# pa.net
KiCad netlist of a schematic drawn in Altium Designer
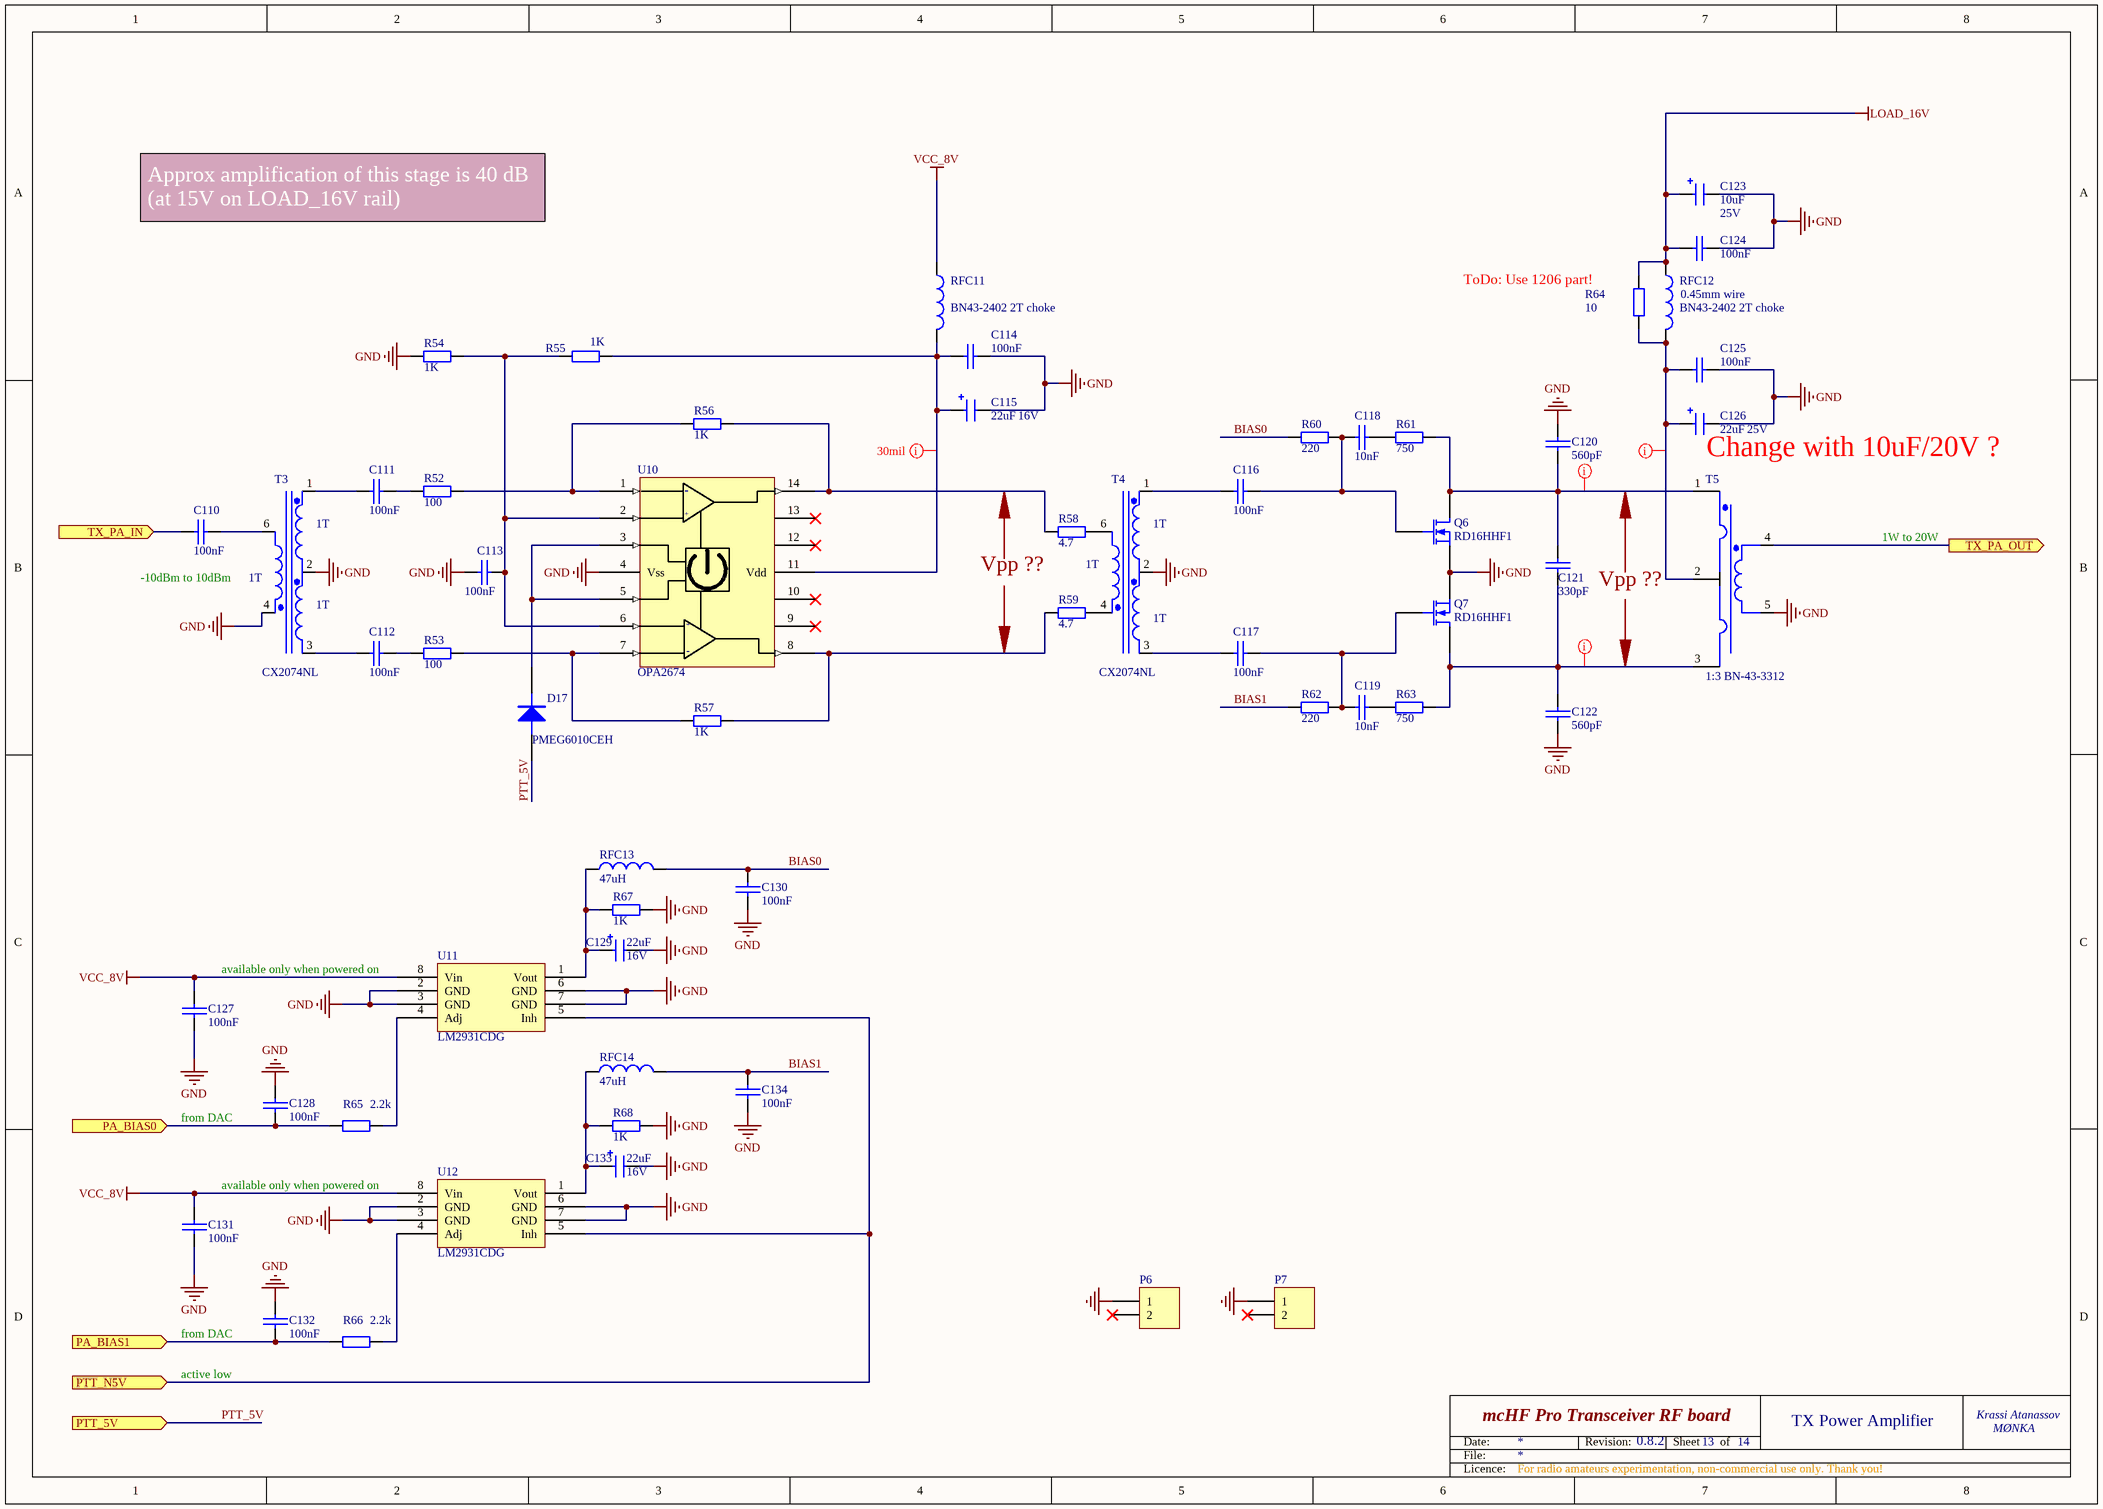
[diagram p0: pa.SchDoc]

(export (version "E")
  (design (tool "Eeschema 10.0.6"))
  (components
    (comp (ref "C110")
      (value "100nF")
      (footprint "0805")
      (description "Capacitor")
      (libsource (lib "mcHF_rf") (part "CAP"))
    )
    (comp (ref "C111")
      (value "100nF")
      (footprint "0805")
      (description "Capacitor")
      (fields (field (name "VOLTAGE") "100V"))
      (libsource (lib "mcHF_rf") (part "CAP"))
    )
    (comp (ref "C112")
      (value "100nF")
      (footprint "0805")
      (description "Capacitor")
      (fields (field (name "VOLTAGE") "100V"))
      (libsource (lib "mcHF_rf") (part "CAP"))
    )
    (comp (ref "C113")
      (value "100nF")
      (footprint "0805")
      (description "Capacitor")
      (fields (field (name "VOLTAGE") "100V"))
      (libsource (lib "mcHF_rf") (part "CAP"))
    )
    (comp (ref "C114")
      (value "100nF")
      (footprint "0805")
      (description "Capacitor")
      (fields (field (name "VOLTAGE") "100V"))
      (libsource (lib "mcHF_rf") (part "CAP"))
    )
    (comp (ref "C115")
      (value "22uF")
      (footprint "1206_Elec_Cap")
      (description "Electrolitic capacitor")
      (fields (field (name "VOLTAGE") "16V"))
      (libsource (lib "mcHF_rf") (part "CAP-POL"))
    )
    (comp (ref "C116")
      (value "100nF")
      (footprint "0805")
      (description "Capacitor")
      (fields (field (name "VOLTAGE") "100V"))
      (libsource (lib "mcHF_rf") (part "CAP"))
    )
    (comp (ref "C117")
      (value "100nF")
      (footprint "0805")
      (description "Capacitor")
      (fields (field (name "VOLTAGE") "100V"))
      (libsource (lib "mcHF_rf") (part "CAP"))
    )
    (comp (ref "C118")
      (value "10nF")
      (footprint "0805")
      (description "Capacitor")
      (fields (field (name "VOLTAGE") "100V"))
      (libsource (lib "mcHF_rf") (part "CAP"))
    )
    (comp (ref "C119")
      (value "10nF")
      (footprint "0805")
      (description "Capacitor")
      (fields (field (name "VOLTAGE") "100V"))
      (libsource (lib "mcHF_rf") (part "CAP"))
    )
    (comp (ref "C120")
      (value "560pF")
      (footprint "0805")
      (description "Capacitor")
      (fields (field (name "VOLTAGE") "100V"))
      (libsource (lib "mcHF_rf") (part "CAP"))
    )
    (comp (ref "C121")
      (value "330pF")
      (footprint "0805")
      (description "Capacitor")
      (fields (field (name "VOLTAGE") "100V"))
      (libsource (lib "mcHF_rf") (part "CAP"))
    )
    (comp (ref "C122")
      (value "560pF")
      (footprint "0805")
      (description "Capacitor")
      (fields (field (name "VOLTAGE") "100V"))
      (libsource (lib "mcHF_rf") (part "CAP"))
    )
    (comp (ref "C123")
      (value "10uF")
      (footprint "1206_Elec_Cap")
      (description "Electrolitic capacitor")
      (fields (field (name "VOLTAGE") "25V"))
      (libsource (lib "mcHF_rf") (part "CAP-POL"))
    )
    (comp (ref "C124")
      (value "100nF")
      (footprint "0805")
      (description "Capacitor")
      (fields (field (name "VOLTAGE") "100V"))
      (libsource (lib "mcHF_rf") (part "CAP"))
    )
    (comp (ref "C125")
      (value "100nF")
      (footprint "0805")
      (description "Capacitor")
      (fields (field (name "VOLTAGE") "100V"))
      (libsource (lib "mcHF_rf") (part "CAP"))
    )
    (comp (ref "C126")
      (value "22uF")
      (footprint "1206_Elec_Cap")
      (description "Electrolitic capacitor")
      (fields (field (name "VOLTAGE") "25V"))
      (libsource (lib "mcHF_rf") (part "CAP-POL"))
    )
    (comp (ref "C127")
      (value "100nF")
      (footprint "0805")
      (description "Capacitor")
      (fields (field (name "VOLTAGE") "100V"))
      (libsource (lib "mcHF_rf") (part "CAP"))
    )
    (comp (ref "C128")
      (value "100nF")
      (footprint "0805")
      (description "Capacitor")
      (libsource (lib "mcHF_rf") (part "CAP"))
    )
    (comp (ref "C129")
      (value "22uF")
      (footprint "1206_Elec_Cap")
      (description "Electrolitic capacitor")
      (fields (field (name "VOLTAGE") "16V"))
      (libsource (lib "mcHF_rf") (part "CAP-POL"))
    )
    (comp (ref "C130")
      (value "100nF")
      (footprint "0805")
      (description "Capacitor")
      (fields (field (name "VOLTAGE") "100V"))
      (libsource (lib "mcHF_rf") (part "CAP"))
    )
    (comp (ref "C131")
      (value "100nF")
      (footprint "0805")
      (description "Capacitor")
      (fields (field (name "VOLTAGE") "100V"))
      (libsource (lib "mcHF_rf") (part "CAP"))
    )
    (comp (ref "C132")
      (value "100nF")
      (footprint "0805")
      (description "Capacitor")
      (libsource (lib "mcHF_rf") (part "CAP"))
    )
    (comp (ref "C133")
      (value "22uF")
      (footprint "1206_Elec_Cap")
      (description "Electrolitic capacitor")
      (fields (field (name "VOLTAGE") "16V"))
      (libsource (lib "mcHF_rf") (part "CAP-POL"))
    )
    (comp (ref "C134")
      (value "100nF")
      (footprint "0805")
      (description "Capacitor")
      (fields (field (name "VOLTAGE") "100V"))
      (libsource (lib "mcHF_rf") (part "CAP"))
    )
    (comp (ref "D17")
      (value "PMEG6010CEH")
      (footprint "SOD87")
      (description "DIODE, SCHOTTKY, 1A, 60V, SOD-123F")
      (libsource (lib "mcHF_rf") (part "PMEG6010CEH"))
    )
    (comp (ref "P6")
      (value "Header 2")
      (footprint "SIP2")
      (description "Header, 2-Pin")
      (libsource (lib "__ui") (part "Header 2"))
    )
    (comp (ref "P7")
      (value "Header 2")
      (footprint "SIP2")
      (description "Header, 2-Pin")
      (libsource (lib "__ui") (part "Header 2"))
    )
    (comp (ref "Q6")
      (value "RD16HHF1")
      (footprint "TO-220RF_flat")
      (description "Silicon RF Power MOS FET")
      (libsource (lib "M_RF") (part "RD16HHF1"))
    )
    (comp (ref "Q7")
      (value "RD16HHF1")
      (footprint "TO-220RF_flat")
      (description "Silicon RF Power MOS FET")
      (libsource (lib "M_RF") (part "RD16HHF1"))
    )
    (comp (ref "R52")
      (value "100")
      (footprint "0805")
      (description "Resistor")
      (libsource (lib "mcHF_rf") (part "RES"))
    )
    (comp (ref "R53")
      (value "100")
      (footprint "0805")
      (description "Resistor")
      (libsource (lib "mcHF_rf") (part "RES"))
    )
    (comp (ref "R54")
      (value "1K")
      (footprint "0805")
      (description "Resistor")
      (libsource (lib "") (part "RES_1"))
    )
    (comp (ref "R55")
      (value "1K")
      (footprint "0805")
      (description "Resistor")
      (libsource (lib "mcHF_rf") (part "RES"))
    )
    (comp (ref "R56")
      (value "1K")
      (footprint "0805")
      (description "Resistor")
      (libsource (lib "mcHF_rf") (part "RES"))
    )
    (comp (ref "R57")
      (value "1K")
      (footprint "0805")
      (description "Resistor")
      (libsource (lib "mcHF_rf") (part "RES"))
    )
    (comp (ref "R58")
      (value "4.7")
      (footprint "0805")
      (description "Resistor")
      (libsource (lib "mcHF_rf") (part "RES"))
    )
    (comp (ref "R59")
      (value "4.7")
      (footprint "0805")
      (description "Resistor")
      (libsource (lib "mcHF_rf") (part "RES"))
    )
    (comp (ref "R60")
      (value "220")
      (footprint "0805")
      (description "Resistor")
      (libsource (lib "mcHF_rf") (part "RES"))
    )
    (comp (ref "R61")
      (value "750")
      (footprint "0805")
      (description "Resistor")
      (libsource (lib "mcHF_rf") (part "RES"))
    )
    (comp (ref "R62")
      (value "220")
      (footprint "0805")
      (description "Resistor")
      (libsource (lib "mcHF_rf") (part "RES"))
    )
    (comp (ref "R63")
      (value "750")
      (footprint "0805")
      (description "Resistor")
      (libsource (lib "mcHF_rf") (part "RES"))
    )
    (comp (ref "R64")
      (value "10")
      (footprint "0805")
      (description "Resistor")
      (libsource (lib "") (part "RES_2"))
    )
    (comp (ref "R65")
      (value "2.2k")
      (footprint "0805")
      (description "Resistor")
      (libsource (lib "") (part "RES_1"))
    )
    (comp (ref "R66")
      (value "2.2k")
      (footprint "0805")
      (description "Resistor")
      (libsource (lib "") (part "RES_1"))
    )
    (comp (ref "R67")
      (value "1K")
      (footprint "0805")
      (description "Resistor")
      (libsource (lib "mcHF_rf") (part "RES"))
    )
    (comp (ref "R68")
      (value "1K")
      (footprint "0805")
      (description "Resistor")
      (libsource (lib "mcHF_rf") (part "RES"))
    )
    (comp (ref "RFC11")
      (value "BN43-2402 2T choke")
      (footprint "F_Bead")
      (description "BN43-2402 1t choke")
      (libsource (lib "mcHF_rf") (part "FER_BEAD"))
    )
    (comp (ref "RFC12")
      (value "BN43-2402 2T choke")
      (footprint "F_Bead")
      (description "BN43-2402 1t choke")
      (libsource (lib "mcHF_rf") (part "FER_BEAD"))
    )
    (comp (ref "RFC13")
      (value "47uH")
      (footprint "0805")
      (description "INDUCTOR, SIGNAL LINE, 4.7UH, 1005")
      (libsource (lib "mcHF_rf") (part "TDK-NLV25T"))
    )
    (comp (ref "RFC14")
      (value "47uH")
      (footprint "0805")
      (description "INDUCTOR, SIGNAL LINE, 4.7UH, 1005")
      (libsource (lib "mcHF_rf") (part "TDK-NLV25T"))
    )
    (comp (ref "T3")
      (value "CX2074NL")
      (footprint "SOP5_NEW1")
      (description "Transformer 4:1")
      (libsource (lib "mcHF_rf") (part "CX2074NL"))
    )
    (comp (ref "T4")
      (value "CX2074NL")
      (footprint "SOP5_NEW1")
      (description "Transformer 4:1")
      (libsource (lib "mcHF_rf") (part "CX2074NL"))
    )
    (comp (ref "T5")
      (value "1:3 BN-43-3312")
      (footprint "PA_OUT_TRM")
      (description "1:3 BN-43-3312 transformer")
      (libsource (lib "__rf") (part "PA_OUT_TR"))
    )
    (comp (ref "U10")
      (value "OPA2674")
      (footprint "SO-14-PRO")
      (description "Dual Wideband, High Output Current\r\nOperational Amplifier with Current Limit")
      (libsource (lib "__rf") (part "OPA2674"))
    )
    (comp (ref "U11")
      (value "LM2931CDG")
      (footprint "SO-8-PRO")
      (description "100 mA, Adjustable Output,  LDO Voltage Regulator with  60 V Load Dump Protection")
      (libsource (lib "mcHF_rf") (part "LM2931CDG"))
    )
    (comp (ref "U12")
      (value "LM2931CDG")
      (footprint "SO-8-PRO")
      (description "100 mA, Adjustable Output,  LDO Voltage Regulator with  60 V Load Dump Protection")
      (libsource (lib "mcHF_rf") (part "LM2931CDG"))
    )
  )
  (nets
    (net (code "1") (name "/BIAS0") (class "Default")
      (node (ref "C130") (pin "2") (pinfunction "2_2") (pintype "passive"))
      (node (ref "R60") (pin "2") (pinfunction "2_2") (pintype "passive"))
      (node (ref "RFC13") (pin "2") (pinfunction "2_2") (pintype "passive"))
    )
    (net (code "2") (name "/BIAS1") (class "Default")
      (node (ref "C134") (pin "2") (pinfunction "2_2") (pintype "passive"))
      (node (ref "R62") (pin "2") (pinfunction "2_2") (pintype "passive"))
      (node (ref "RFC14") (pin "2") (pinfunction "2_2") (pintype "passive"))
    )
    (net (code "3") (name "/PA_BIAS0") (class "Default")
      (node (ref "C128") (pin "1") (pinfunction "1_1") (pintype "passive"))
      (node (ref "R65") (pin "1") (pinfunction "1_1") (pintype "passive"))
    )
    (net (code "4") (name "/PA_BIAS1") (class "Default")
      (node (ref "C132") (pin "2") (pinfunction "2_2") (pintype "passive"))
      (node (ref "R66") (pin "1") (pinfunction "1_1") (pintype "passive"))
    )
    (net (code "5") (name "/PTT_5V") (class "Default")
      (node (ref "D17") (pin "1") (pinfunction "A_1") (pintype "passive"))
    )
    (net (code "6") (name "/PTT_N5V") (class "Default")
      (node (ref "U11") (pin "5") (pinfunction "Inh_5") (pintype "passive"))
      (node (ref "U12") (pin "5") (pinfunction "Inh_5") (pintype "passive"))
    )
    (net (code "7") (name "/TX_PA_IN") (class "Default")
      (node (ref "C110") (pin "2") (pinfunction "2_2") (pintype "passive"))
    )
    (net (code "8") (name "/TX_PA_OUT") (class "Default")
      (node (ref "T5") (pin "4") (pinfunction "Sec+_4") (pintype "passive"))
    )
    (net (code "9") (name "GND") (class "Default")
      (node (ref "C113") (pin "1") (pinfunction "1_1") (pintype "passive"))
      (node (ref "C114") (pin "1") (pinfunction "1_1") (pintype "passive"))
      (node (ref "C115") (pin "2") (pinfunction "2_2") (pintype "passive"))
      (node (ref "C120") (pin "1") (pinfunction "1_1") (pintype "passive"))
      (node (ref "C122") (pin "2") (pinfunction "2_2") (pintype "passive"))
      (node (ref "C123") (pin "2") (pinfunction "2_2") (pintype "passive"))
      (node (ref "C124") (pin "1") (pinfunction "1_1") (pintype "passive"))
      (node (ref "C125") (pin "1") (pinfunction "1_1") (pintype "passive"))
      (node (ref "C126") (pin "2") (pinfunction "2_2") (pintype "passive"))
      (node (ref "C127") (pin "2") (pinfunction "2_2") (pintype "passive"))
      (node (ref "C128") (pin "2") (pinfunction "2_2") (pintype "passive"))
      (node (ref "C129") (pin "2") (pinfunction "2_2") (pintype "passive"))
      (node (ref "C130") (pin "1") (pinfunction "1_1") (pintype "passive"))
      (node (ref "C131") (pin "2") (pinfunction "2_2") (pintype "passive"))
      (node (ref "C132") (pin "1") (pinfunction "1_1") (pintype "passive"))
      (node (ref "C133") (pin "2") (pinfunction "2_2") (pintype "passive"))
      (node (ref "C134") (pin "1") (pinfunction "1_1") (pintype "passive"))
      (node (ref "P6") (pin "1") (pinfunction "1_1") (pintype "passive"))
      (node (ref "P7") (pin "1") (pinfunction "1_1") (pintype "passive"))
      (node (ref "Q6") (pin "2") (pinfunction "S_2") (pintype "passive"))
      (node (ref "Q7") (pin "2") (pinfunction "S_2") (pintype "passive"))
      (node (ref "R54") (pin "1") (pinfunction "1_1") (pintype "passive"))
      (node (ref "R67") (pin "1") (pinfunction "1_1") (pintype "passive"))
      (node (ref "R68") (pin "1") (pinfunction "1_1") (pintype "passive"))
      (node (ref "T3") (pin "2") (pinfunction "SecCmn_2") (pintype "passive"))
      (node (ref "T3") (pin "4") (pinfunction "Pri-_4") (pintype "passive"))
      (node (ref "T4") (pin "2") (pinfunction "SecCmn_2") (pintype "passive"))
      (node (ref "T5") (pin "5") (pinfunction "Sec-_5") (pintype "passive"))
      (node (ref "U10") (pin "4") (pinfunction "Vss_4") (pintype "power_in"))
      (node (ref "U11") (pin "2") (pinfunction "GND_2") (pintype "passive"))
      (node (ref "U11") (pin "3") (pinfunction "GND_3") (pintype "passive"))
      (node (ref "U11") (pin "6") (pinfunction "GND_6") (pintype "passive"))
      (node (ref "U11") (pin "7") (pinfunction "GND_7") (pintype "passive"))
      (node (ref "U12") (pin "2") (pinfunction "GND_2") (pintype "passive"))
      (node (ref "U12") (pin "3") (pinfunction "GND_3") (pintype "passive"))
      (node (ref "U12") (pin "6") (pinfunction "GND_6") (pintype "passive"))
      (node (ref "U12") (pin "7") (pinfunction "GND_7") (pintype "passive"))
    )
    (net (code "10") (name "LOAD_16V") (class "Default")
      (node (ref "C123") (pin "1") (pinfunction "1_1") (pintype "passive"))
      (node (ref "C124") (pin "2") (pinfunction "2_2") (pintype "passive"))
      (node (ref "R64") (pin "2") (pinfunction "2_2") (pintype "passive"))
      (node (ref "RFC12") (pin "1") (pinfunction "1_1") (pintype "passive"))
    )
    (net (code "11") (name "Net-(C111-Pad2)") (class "Default")
      (node (ref "C111") (pin "2") (pinfunction "2_2") (pintype "passive"))
      (node (ref "R52") (pin "2") (pinfunction "2_2") (pintype "passive"))
    )
    (net (code "12") (name "Net-(C112-Pad2)") (class "Default")
      (node (ref "C112") (pin "2") (pinfunction "2_2") (pintype "passive"))
      (node (ref "R53") (pin "2") (pinfunction "2_2") (pintype "passive"))
    )
    (net (code "13") (name "Net-(C113-Pad2)") (class "Default")
      (node (ref "C113") (pin "2") (pinfunction "2_2") (pintype "passive"))
      (node (ref "R54") (pin "2") (pinfunction "2_2") (pintype "passive"))
      (node (ref "R55") (pin "2") (pinfunction "2_2") (pintype "passive"))
      (node (ref "U10") (pin "2") (pintype "input"))
      (node (ref "U10") (pin "6") (pintype "input"))
    )
    (net (code "14") (name "Net-(C118-Pad2)") (class "Default")
      (node (ref "C118") (pin "2") (pinfunction "2_2") (pintype "passive"))
      (node (ref "R61") (pin "2") (pinfunction "2_2") (pintype "passive"))
    )
    (net (code "15") (name "Net-(C119-Pad2)") (class "Default")
      (node (ref "C119") (pin "2") (pinfunction "2_2") (pintype "passive"))
      (node (ref "R63") (pin "2") (pinfunction "2_2") (pintype "passive"))
    )
    (net (code "16") (name "Net-(D17-K)") (class "Default")
      (node (ref "D17") (pin "2") (pinfunction "K_2") (pintype "passive"))
      (node (ref "U10") (pin "3") (pintype "input"))
      (node (ref "U10") (pin "5") (pintype "input"))
    )
    (net (code "17") (name "Net-(Q6-D)") (class "Default")
      (node (ref "C120") (pin "2") (pinfunction "2_2") (pintype "passive"))
      (node (ref "C121") (pin "1") (pinfunction "1_1") (pintype "passive"))
      (node (ref "Q6") (pin "3") (pinfunction "D_3") (pintype "passive"))
      (node (ref "R61") (pin "1") (pinfunction "1_1") (pintype "passive"))
      (node (ref "T5") (pin "1") (pinfunction "Pri_0_deg_1") (pintype "passive"))
    )
    (net (code "18") (name "Net-(Q6-G)") (class "Default")
      (node (ref "C116") (pin "1") (pinfunction "1_1") (pintype "passive"))
      (node (ref "C118") (pin "1") (pinfunction "1_1") (pintype "passive"))
      (node (ref "Q6") (pin "1") (pinfunction "G_1") (pintype "passive"))
      (node (ref "R60") (pin "1") (pinfunction "1_1") (pintype "passive"))
    )
    (net (code "19") (name "Net-(Q7-D)") (class "Default")
      (node (ref "C121") (pin "2") (pinfunction "2_2") (pintype "passive"))
      (node (ref "C122") (pin "1") (pinfunction "1_1") (pintype "passive"))
      (node (ref "Q7") (pin "3") (pinfunction "D_3") (pintype "passive"))
      (node (ref "R63") (pin "1") (pinfunction "1_1") (pintype "passive"))
      (node (ref "T5") (pin "3") (pinfunction "Pri_180_deg_3") (pintype "passive"))
    )
    (net (code "20") (name "Net-(Q7-G)") (class "Default")
      (node (ref "C117") (pin "1") (pinfunction "1_1") (pintype "passive"))
      (node (ref "C119") (pin "1") (pinfunction "1_1") (pintype "passive"))
      (node (ref "Q7") (pin "1") (pinfunction "G_1") (pintype "passive"))
      (node (ref "R62") (pin "1") (pinfunction "1_1") (pintype "passive"))
    )
    (net (code "21") (name "Net-(R52-Pad1)") (class "Default")
      (node (ref "R52") (pin "1") (pinfunction "1_1") (pintype "passive"))
      (node (ref "R56") (pin "2") (pinfunction "2_2") (pintype "passive"))
      (node (ref "U10") (pin "1") (pintype "input"))
    )
    (net (code "22") (name "Net-(R53-Pad1)") (class "Default")
      (node (ref "R53") (pin "1") (pinfunction "1_1") (pintype "passive"))
      (node (ref "R57") (pin "2") (pinfunction "2_2") (pintype "passive"))
      (node (ref "U10") (pin "7") (pintype "input"))
    )
    (net (code "23") (name "Net-(R56-Pad1)") (class "Default")
      (node (ref "R56") (pin "1") (pinfunction "1_1") (pintype "passive"))
      (node (ref "R58") (pin "2") (pinfunction "2_2") (pintype "passive"))
      (node (ref "U10") (pin "14") (pintype "output"))
    )
    (net (code "24") (name "Net-(R57-Pad1)") (class "Default")
      (node (ref "R57") (pin "1") (pinfunction "1_1") (pintype "passive"))
      (node (ref "R59") (pin "2") (pinfunction "2_2") (pintype "passive"))
      (node (ref "U10") (pin "8") (pintype "output"))
    )
    (net (code "25") (name "Net-(T3-Pri+)") (class "Default")
      (node (ref "C110") (pin "1") (pinfunction "1_1") (pintype "passive"))
      (node (ref "T3") (pin "6") (pinfunction "Pri+_6") (pintype "passive"))
    )
    (net (code "26") (name "Net-(T3-Sec0)") (class "Default")
      (node (ref "C111") (pin "1") (pinfunction "1_1") (pintype "passive"))
      (node (ref "T3") (pin "1") (pinfunction "Sec0_1") (pintype "passive"))
    )
    (net (code "27") (name "Net-(T3-Sec180)") (class "Default")
      (node (ref "C112") (pin "1") (pinfunction "1_1") (pintype "passive"))
      (node (ref "T3") (pin "3") (pinfunction "Sec180_3") (pintype "passive"))
    )
    (net (code "28") (name "Net-(T4-Pri+)") (class "Default")
      (node (ref "R58") (pin "1") (pinfunction "1_1") (pintype "passive"))
      (node (ref "T4") (pin "6") (pinfunction "Pri+_6") (pintype "passive"))
    )
    (net (code "29") (name "Net-(T4-Pri-)") (class "Default")
      (node (ref "R59") (pin "1") (pinfunction "1_1") (pintype "passive"))
      (node (ref "T4") (pin "4") (pinfunction "Pri-_4") (pintype "passive"))
    )
    (net (code "30") (name "Net-(T4-Sec0)") (class "Default")
      (node (ref "C116") (pin "2") (pinfunction "2_2") (pintype "passive"))
      (node (ref "T4") (pin "1") (pinfunction "Sec0_1") (pintype "passive"))
    )
    (net (code "31") (name "Net-(T4-Sec180)") (class "Default")
      (node (ref "C117") (pin "2") (pinfunction "2_2") (pintype "passive"))
      (node (ref "T4") (pin "3") (pinfunction "Sec180_3") (pintype "passive"))
    )
    (net (code "32") (name "Net-(T5-Pri_Common)") (class "Default")
      (node (ref "C125") (pin "2") (pinfunction "2_2") (pintype "passive"))
      (node (ref "C126") (pin "1") (pinfunction "1_1") (pintype "passive"))
      (node (ref "R64") (pin "1") (pinfunction "1_1") (pintype "passive"))
      (node (ref "RFC12") (pin "2") (pinfunction "2_2") (pintype "passive"))
      (node (ref "T5") (pin "2") (pinfunction "Pri_Common_2") (pintype "passive"))
    )
    (net (code "33") (name "Net-(U10-Vdd)") (class "Default")
      (node (ref "C114") (pin "2") (pinfunction "2_2") (pintype "passive"))
      (node (ref "C115") (pin "1") (pinfunction "1_1") (pintype "passive"))
      (node (ref "R55") (pin "1") (pinfunction "1_1") (pintype "passive"))
      (node (ref "RFC11") (pin "2") (pinfunction "2_2") (pintype "passive"))
      (node (ref "U10") (pin "11") (pinfunction "Vdd_11") (pintype "power_in"))
    )
    (net (code "34") (name "Net-(U11-Adj)") (class "Default")
      (node (ref "R65") (pin "2") (pinfunction "2_2") (pintype "passive"))
      (node (ref "U11") (pin "4") (pinfunction "Adj_4") (pintype "passive"))
    )
    (net (code "35") (name "Net-(U11-Vout)") (class "Default")
      (node (ref "C129") (pin "1") (pinfunction "1_1") (pintype "passive"))
      (node (ref "R67") (pin "2") (pinfunction "2_2") (pintype "passive"))
      (node (ref "RFC13") (pin "1") (pinfunction "1_1") (pintype "passive"))
      (node (ref "U11") (pin "1") (pinfunction "Vout_1") (pintype "passive"))
    )
    (net (code "36") (name "Net-(U12-Adj)") (class "Default")
      (node (ref "R66") (pin "2") (pinfunction "2_2") (pintype "passive"))
      (node (ref "U12") (pin "4") (pinfunction "Adj_4") (pintype "passive"))
    )
    (net (code "37") (name "Net-(U12-Vout)") (class "Default")
      (node (ref "C133") (pin "1") (pinfunction "1_1") (pintype "passive"))
      (node (ref "R68") (pin "2") (pinfunction "2_2") (pintype "passive"))
      (node (ref "RFC14") (pin "1") (pinfunction "1_1") (pintype "passive"))
      (node (ref "U12") (pin "1") (pinfunction "Vout_1") (pintype "passive"))
    )
    (net (code "38") (name "VCC_8V") (class "Default")
      (node (ref "C127") (pin "1") (pinfunction "1_1") (pintype "passive"))
      (node (ref "C131") (pin "1") (pinfunction "1_1") (pintype "passive"))
      (node (ref "RFC11") (pin "1") (pinfunction "1_1") (pintype "passive"))
      (node (ref "U11") (pin "8") (pinfunction "Vin_8") (pintype "passive"))
      (node (ref "U12") (pin "8") (pinfunction "Vin_8") (pintype "passive"))
    )
    (net (code "39") (name "unconnected-(P6-Pad2)") (class "Default")
      (node (ref "P6") (pin "2") (pinfunction "2_2") (pintype "passive+no_connect"))
    )
    (net (code "40") (name "unconnected-(P7-Pad2)") (class "Default")
      (node (ref "P7") (pin "2") (pinfunction "2_2") (pintype "passive+no_connect"))
    )
    (net (code "41") (name "unconnected-(U10-Pad9)") (class "Default")
      (node (ref "U10") (pin "9") (pintype "passive+no_connect"))
    )
    (net (code "42") (name "unconnected-(U10-Pad10)") (class "Default")
      (node (ref "U10") (pin "10") (pintype "passive+no_connect"))
    )
    (net (code "43") (name "unconnected-(U10-Pad12)") (class "Default")
      (node (ref "U10") (pin "12") (pintype "passive+no_connect"))
    )
    (net (code "44") (name "unconnected-(U10-Pad13)") (class "Default")
      (node (ref "U10") (pin "13") (pintype "passive+no_connect"))
    )
  )
)
